# Optokoppleradapter_Spannungsmessung.net
KiCad netlist of a schematic drawn in EAGLE
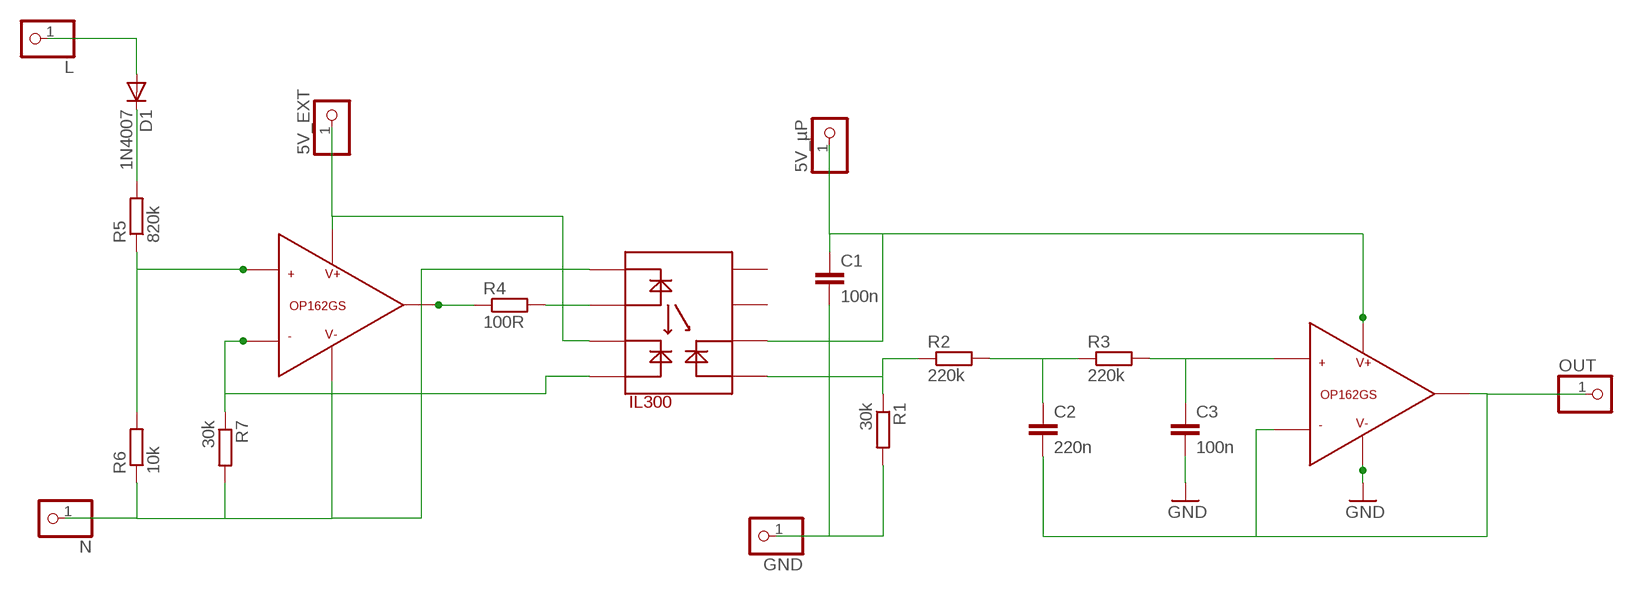
[diagram p0: schematic, sheet 1]

(export (version "E")
  (design (tool "Eeschema 10.0.6"))
  (components
    (comp (ref "5V_EXT")
      (value "PINHD-1X1")
      (footprint "eagle-import:1X01")
      (libsource (lib "eagle-import") (part "PINHD-1X1"))
    )
    (comp (ref "5V_µP")
      (value "PINHD-1X1")
      (footprint "eagle-import:1X01")
      (libsource (lib "eagle-import") (part "PINHD-1X1"))
    )
    (comp (ref "C1")
      (value "100n")
      (footprint "eagle-import:C0805")
      (libsource (lib "eagle-import") (part "C-EUC0805"))
    )
    (comp (ref "C2")
      (value "220n")
      (footprint "eagle-import:C0805")
      (libsource (lib "eagle-import") (part "C-EUC0805"))
    )
    (comp (ref "C3")
      (value "100n")
      (footprint "eagle-import:C0805")
      (libsource (lib "eagle-import") (part "C-EUC0805"))
    )
    (comp (ref "D1")
      (value "1N4007")
      (footprint "eagle-import:DO35-7")
      (libsource (lib "eagle-import") (part "1N4148DO35-7"))
    )
    (comp (ref "GND")
      (value "PINHD-1X1")
      (footprint "eagle-import:1X01")
      (libsource (lib "eagle-import") (part "PINHD-1X1"))
    )
    (comp (ref "L")
      (value "PINHD-1X1")
      (footprint "eagle-import:1X01")
      (libsource (lib "eagle-import") (part "PINHD-1X1"))
    )
    (comp (ref "N")
      (value "PINHD-1X1")
      (footprint "eagle-import:1X01")
      (libsource (lib "eagle-import") (part "PINHD-1X1"))
    )
    (comp (ref "OUT")
      (value "PINHD-1X1")
      (footprint "eagle-import:1X01")
      (libsource (lib "eagle-import") (part "PINHD-1X1"))
    )
    (comp (ref "R1")
      (value "30k")
      (footprint "eagle-import:R0805")
      (libsource (lib "eagle-import") (part "R-EU_R0805"))
    )
    (comp (ref "R2")
      (value "220k")
      (footprint "eagle-import:R0805")
      (libsource (lib "eagle-import") (part "R-EU_R0805"))
    )
    (comp (ref "R3")
      (value "220k")
      (footprint "eagle-import:R0805")
      (libsource (lib "eagle-import") (part "R-EU_R0805"))
    )
    (comp (ref "R4")
      (value "100R")
      (footprint "eagle-import:R0805")
      (libsource (lib "eagle-import") (part "R-EU_R0805"))
    )
    (comp (ref "R5")
      (value "820k")
      (footprint "eagle-import:0207_7")
      (libsource (lib "eagle-import") (part "R-EU_0207/7"))
    )
    (comp (ref "R6")
      (value "10k")
      (footprint "eagle-import:0207_7")
      (libsource (lib "eagle-import") (part "R-EU_0207/7"))
    )
    (comp (ref "R7")
      (value "30k")
      (footprint "eagle-import:0207_7")
      (libsource (lib "eagle-import") (part "R-EU_0207/7"))
    )
    (comp (ref "U$1")
      (value "IL300")
      (footprint "eagle-import:DIP8")
      (libsource (lib "eagle-import") (part "IL300"))
    )
    (comp (ref "U$2")
      (value "OP162GS")
      (footprint "eagle-import:SOIC_N")
      (libsource (lib "eagle-import") (part "OP162GS"))
    )
    (comp (ref "U$3")
      (value "OP162GS")
      (footprint "eagle-import:SOIC_N")
      (libsource (lib "eagle-import") (part "OP162GS"))
    )
  )
  (nets
    (net (code "1") (name "GND") (class "Default")
      (node (ref "C1") (pin "2") (pinfunction "2_2") (pintype "passive"))
      (node (ref "C3") (pin "2") (pinfunction "2_2") (pintype "passive"))
      (node (ref "GND") (pin "1") (pinfunction "1_1") (pintype "passive"))
      (node (ref "R1") (pin "2") (pinfunction "2_2") (pintype "passive"))
      (node (ref "U$3") (pin "P$4") (pinfunction "V-_P$4") (pintype "bidirectional"))
    )
    (net (code "2") (name "Net-(C2-Pad1)") (class "Default")
      (node (ref "C2") (pin "1") (pinfunction "1_1") (pintype "passive"))
      (node (ref "R2") (pin "2") (pinfunction "2_2") (pintype "passive"))
      (node (ref "R3") (pin "1") (pinfunction "1_1") (pintype "passive"))
    )
    (net (code "3") (name "Net-(D1-PadA)") (class "Default")
      (node (ref "D1") (pin "A") (pinfunction "A_A") (pintype "passive"))
      (node (ref "L") (pin "1") (pinfunction "1_1") (pintype "passive"))
    )
    (net (code "4") (name "Net-(D1-PadC)") (class "Default")
      (node (ref "D1") (pin "C") (pinfunction "C_C") (pintype "passive"))
      (node (ref "R5") (pin "2") (pinfunction "2_2") (pintype "passive"))
    )
    (net (code "5") (name "Net-(R1-Pad1)") (class "Default")
      (node (ref "R1") (pin "1") (pinfunction "1_1") (pintype "passive"))
      (node (ref "R2") (pin "1") (pinfunction "1_1") (pintype "passive"))
      (node (ref "U$1") (pin "P$5") (pinfunction "P$5_P$5") (pintype "bidirectional"))
    )
    (net (code "6") (name "Net-(R4-Pad2)") (class "Default")
      (node (ref "R4") (pin "2") (pinfunction "2_2") (pintype "passive"))
      (node (ref "U$1") (pin "P$2") (pinfunction "P$2_P$2") (pintype "bidirectional"))
    )
    (net (code "7") (name "Net-(U$2-+)") (class "Default")
      (node (ref "R5") (pin "1") (pinfunction "1_1") (pintype "passive"))
      (node (ref "R6") (pin "2") (pinfunction "2_2") (pintype "passive"))
      (node (ref "U$2") (pin "P$3") (pinfunction "+_P$3") (pintype "bidirectional"))
    )
    (net (code "8") (name "Net-(U$2--)") (class "Default")
      (node (ref "R7") (pin "1") (pinfunction "1_1") (pintype "passive"))
      (node (ref "U$1") (pin "P$4") (pinfunction "P$4_P$4") (pintype "bidirectional"))
      (node (ref "U$2") (pin "P$2") (pinfunction "-_P$2") (pintype "bidirectional"))
    )
    (net (code "9") (name "Net-(U$2-OUT)") (class "Default")
      (node (ref "R4") (pin "1") (pinfunction "1_1") (pintype "passive"))
      (node (ref "U$2") (pin "P$6") (pinfunction "OUT_P$6") (pintype "bidirectional"))
    )
    (net (code "10") (name "Net-(U$2-V+)") (class "Default")
      (node (ref "5V_EXT") (pin "1") (pinfunction "1_1") (pintype "passive"))
      (node (ref "U$1") (pin "P$3") (pinfunction "P$3_P$3") (pintype "bidirectional"))
      (node (ref "U$2") (pin "P$7") (pinfunction "V+_P$7") (pintype "bidirectional"))
    )
    (net (code "11") (name "Net-(U$2-V-)") (class "Default")
      (node (ref "N") (pin "1") (pinfunction "1_1") (pintype "passive"))
      (node (ref "R6") (pin "1") (pinfunction "1_1") (pintype "passive"))
      (node (ref "R7") (pin "2") (pinfunction "2_2") (pintype "passive"))
      (node (ref "U$1") (pin "P$1") (pinfunction "P$1_P$1") (pintype "bidirectional"))
      (node (ref "U$2") (pin "P$4") (pinfunction "V-_P$4") (pintype "bidirectional"))
    )
    (net (code "12") (name "Net-(U$3-+)") (class "Default")
      (node (ref "C3") (pin "1") (pinfunction "1_1") (pintype "passive"))
      (node (ref "R3") (pin "2") (pinfunction "2_2") (pintype "passive"))
      (node (ref "U$3") (pin "P$3") (pinfunction "+_P$3") (pintype "bidirectional"))
    )
    (net (code "13") (name "Net-(U$3--)") (class "Default")
      (node (ref "C2") (pin "2") (pinfunction "2_2") (pintype "passive"))
      (node (ref "OUT") (pin "1") (pinfunction "1_1") (pintype "passive"))
      (node (ref "U$3") (pin "P$2") (pinfunction "-_P$2") (pintype "bidirectional"))
      (node (ref "U$3") (pin "P$6") (pinfunction "OUT_P$6") (pintype "bidirectional"))
    )
    (net (code "14") (name "Net-(U$3-V+)") (class "Default")
      (node (ref "5V_µP") (pin "1") (pinfunction "1_1") (pintype "passive"))
      (node (ref "C1") (pin "1") (pinfunction "1_1") (pintype "passive"))
      (node (ref "U$1") (pin "P$6") (pinfunction "P$6_P$6") (pintype "bidirectional"))
      (node (ref "U$3") (pin "P$7") (pinfunction "V+_P$7") (pintype "bidirectional"))
    )
    (net (code "15") (name "unconnected-(U$1-PadP$7)") (class "Default")
      (node (ref "U$1") (pin "P$7") (pinfunction "P$7_P$7") (pintype "bidirectional"))
    )
    (net (code "16") (name "unconnected-(U$1-PadP$8)") (class "Default")
      (node (ref "U$1") (pin "P$8") (pinfunction "P$8_P$8") (pintype "bidirectional"))
    )
  )
)
